# sch_ma_Carte_Puissance.net
KiCad netlist of a schematic drawn in EAGLE
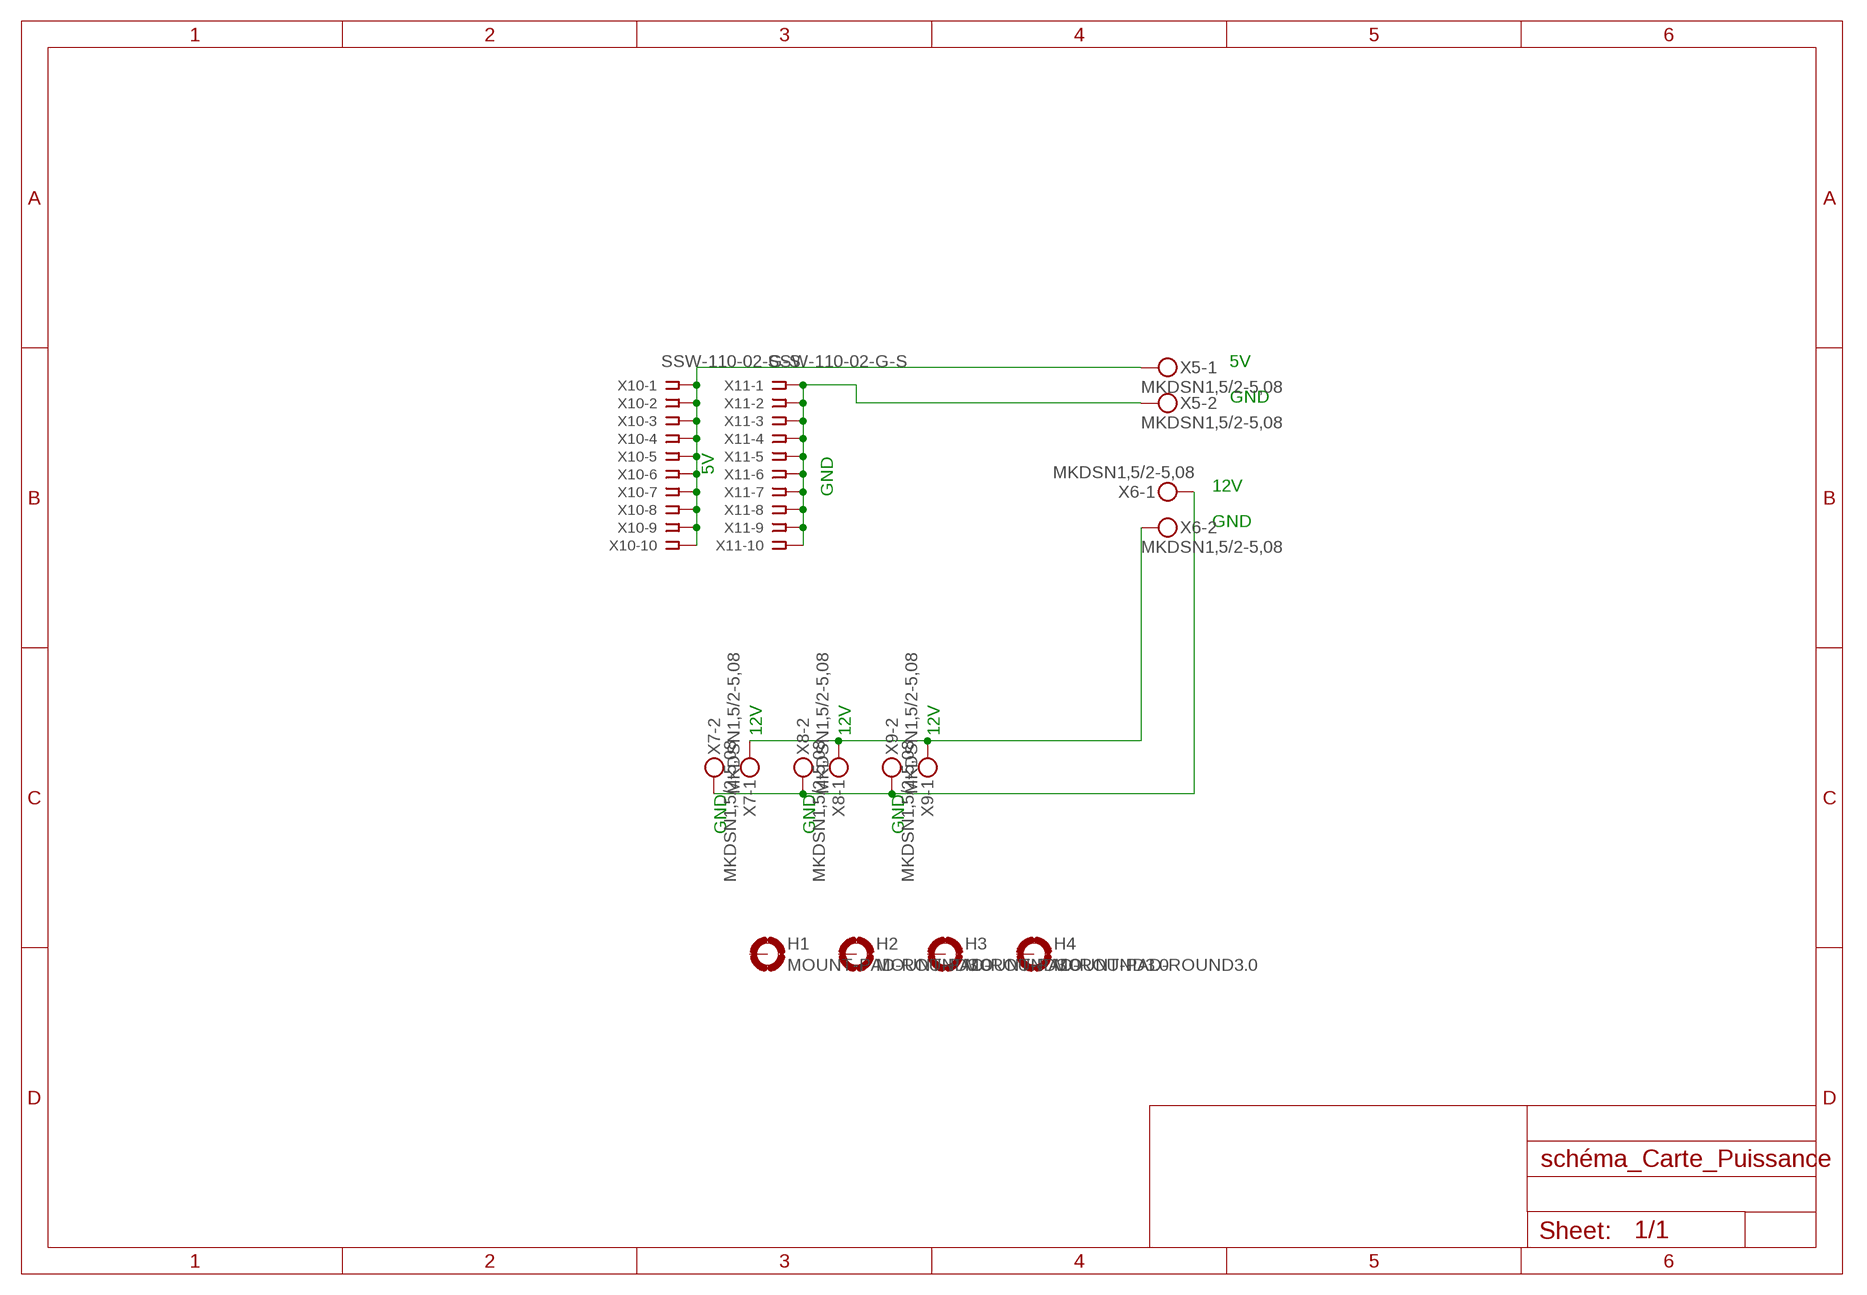
[diagram p0: schematic, sheet 1]

(export (version "E")
  (design (tool "Eeschema 10.0.6"))
  (components
    (comp (ref "H1")
      (value "MOUNT-PAD-ROUND3.0")
      (footprint "eagle-import:3,0-PAD")
      (libsource (lib "eagle-import") (part "MOUNT-PAD-ROUND3.0"))
    )
    (comp (ref "H2")
      (value "MOUNT-PAD-ROUND3.0")
      (footprint "eagle-import:3,0-PAD")
      (libsource (lib "eagle-import") (part "MOUNT-PAD-ROUND3.0"))
    )
    (comp (ref "H3")
      (value "MOUNT-PAD-ROUND3.0")
      (footprint "eagle-import:3,0-PAD")
      (libsource (lib "eagle-import") (part "MOUNT-PAD-ROUND3.0"))
    )
    (comp (ref "H4")
      (value "MOUNT-PAD-ROUND3.0")
      (footprint "eagle-import:3,0-PAD")
      (libsource (lib "eagle-import") (part "MOUNT-PAD-ROUND3.0"))
    )
    (comp (ref "X5")
      (value "MKDSN1,5/2-5,08")
      (footprint "eagle-import:MKDSN1,5_2-5,08")
      (libsource (lib "eagle-import") (part "MKDSN1,5/2-5,08"))
    )
    (comp (ref "X6")
      (value "MKDSN1,5/2-5,08")
      (footprint "eagle-import:MKDSN1,5_2-5,08")
      (libsource (lib "eagle-import") (part "MKDSN1,5/2-5,08"))
    )
    (comp (ref "X7")
      (value "MKDSN1,5/2-5,08")
      (footprint "eagle-import:MKDSN1,5_2-5,08")
      (libsource (lib "eagle-import") (part "MKDSN1,5/2-5,08"))
    )
    (comp (ref "X8")
      (value "MKDSN1,5/2-5,08")
      (footprint "eagle-import:MKDSN1,5_2-5,08")
      (libsource (lib "eagle-import") (part "MKDSN1,5/2-5,08"))
    )
    (comp (ref "X9")
      (value "MKDSN1,5/2-5,08")
      (footprint "eagle-import:MKDSN1,5_2-5,08")
      (libsource (lib "eagle-import") (part "MKDSN1,5/2-5,08"))
    )
    (comp (ref "X10")
      (value "SSW-110-02-G-S")
      (footprint "eagle-import:SSW-110-02-G-S")
      (fields (field (name "MF") "Samtec Inc."))
      (libsource (lib "eagle-import") (part "SSW-110-02-G-S"))
    )
    (comp (ref "X11")
      (value "SSW-110-02-G-S")
      (footprint "eagle-import:SSW-110-02-G-S")
      (fields (field (name "MF") "Samtec Inc."))
      (libsource (lib "eagle-import") (part "SSW-110-02-G-S"))
    )
  )
  (nets
    (net (code "1") (name "Net-(X6A-KL)") (class "Default")
      (node (ref "X6") (pin "1") (pinfunction "KL_1") (pintype "passive"))
      (node (ref "X7") (pin "2") (pinfunction "KL_2") (pintype "passive"))
      (node (ref "X8") (pin "2") (pinfunction "KL_2") (pintype "passive"))
      (node (ref "X9") (pin "2") (pinfunction "KL_2") (pintype "passive"))
    )
    (net (code "2") (name "Net-(X6B-KL)") (class "Default")
      (node (ref "X6") (pin "2") (pinfunction "KL_2") (pintype "passive"))
      (node (ref "X7") (pin "1") (pinfunction "KL_1") (pintype "passive"))
      (node (ref "X8") (pin "1") (pinfunction "KL_1") (pintype "passive"))
      (node (ref "X9") (pin "1") (pinfunction "KL_1") (pintype "passive"))
    )
    (net (code "3") (name "Net-(X10B-1)") (class "Default")
      (node (ref "X10") (pin "1") (pinfunction "1_1") (pintype "passive"))
      (node (ref "X10") (pin "10") (pinfunction "1_10") (pintype "passive"))
      (node (ref "X10") (pin "2") (pinfunction "1_2") (pintype "passive"))
      (node (ref "X10") (pin "3") (pinfunction "1_3") (pintype "passive"))
      (node (ref "X10") (pin "4") (pinfunction "1_4") (pintype "passive"))
      (node (ref "X10") (pin "5") (pinfunction "1_5") (pintype "passive"))
      (node (ref "X10") (pin "6") (pinfunction "1_6") (pintype "passive"))
      (node (ref "X10") (pin "7") (pinfunction "1_7") (pintype "passive"))
      (node (ref "X10") (pin "8") (pinfunction "1_8") (pintype "passive"))
      (node (ref "X10") (pin "9") (pinfunction "1_9") (pintype "passive"))
      (node (ref "X5") (pin "1") (pinfunction "KL_1") (pintype "passive"))
    )
    (net (code "4") (name "Net-(X11B-1)") (class "Default")
      (node (ref "X11") (pin "1") (pinfunction "1_1") (pintype "passive"))
      (node (ref "X11") (pin "10") (pinfunction "1_10") (pintype "passive"))
      (node (ref "X11") (pin "2") (pinfunction "1_2") (pintype "passive"))
      (node (ref "X11") (pin "3") (pinfunction "1_3") (pintype "passive"))
      (node (ref "X11") (pin "4") (pinfunction "1_4") (pintype "passive"))
      (node (ref "X11") (pin "5") (pinfunction "1_5") (pintype "passive"))
      (node (ref "X11") (pin "6") (pinfunction "1_6") (pintype "passive"))
      (node (ref "X11") (pin "7") (pinfunction "1_7") (pintype "passive"))
      (node (ref "X11") (pin "8") (pinfunction "1_8") (pintype "passive"))
      (node (ref "X11") (pin "9") (pinfunction "1_9") (pintype "passive"))
      (node (ref "X5") (pin "2") (pinfunction "KL_2") (pintype "passive"))
    )
    (net (code "5") (name "unconnected-(H1-MOUNT-PadB3,0)") (class "Default")
      (node (ref "H1") (pin "B3,0") (pinfunction "MOUNT_B3,0") (pintype "passive"))
    )
    (net (code "6") (name "unconnected-(H2-MOUNT-PadB3,0)") (class "Default")
      (node (ref "H2") (pin "B3,0") (pinfunction "MOUNT_B3,0") (pintype "passive"))
    )
    (net (code "7") (name "unconnected-(H3-MOUNT-PadB3,0)") (class "Default")
      (node (ref "H3") (pin "B3,0") (pinfunction "MOUNT_B3,0") (pintype "passive"))
    )
    (net (code "8") (name "unconnected-(H4-MOUNT-PadB3,0)") (class "Default")
      (node (ref "H4") (pin "B3,0") (pinfunction "MOUNT_B3,0") (pintype "passive"))
    )
  )
)
